# Esquem_tico.net
KiCad netlist of a schematic drawn in Altium Designer
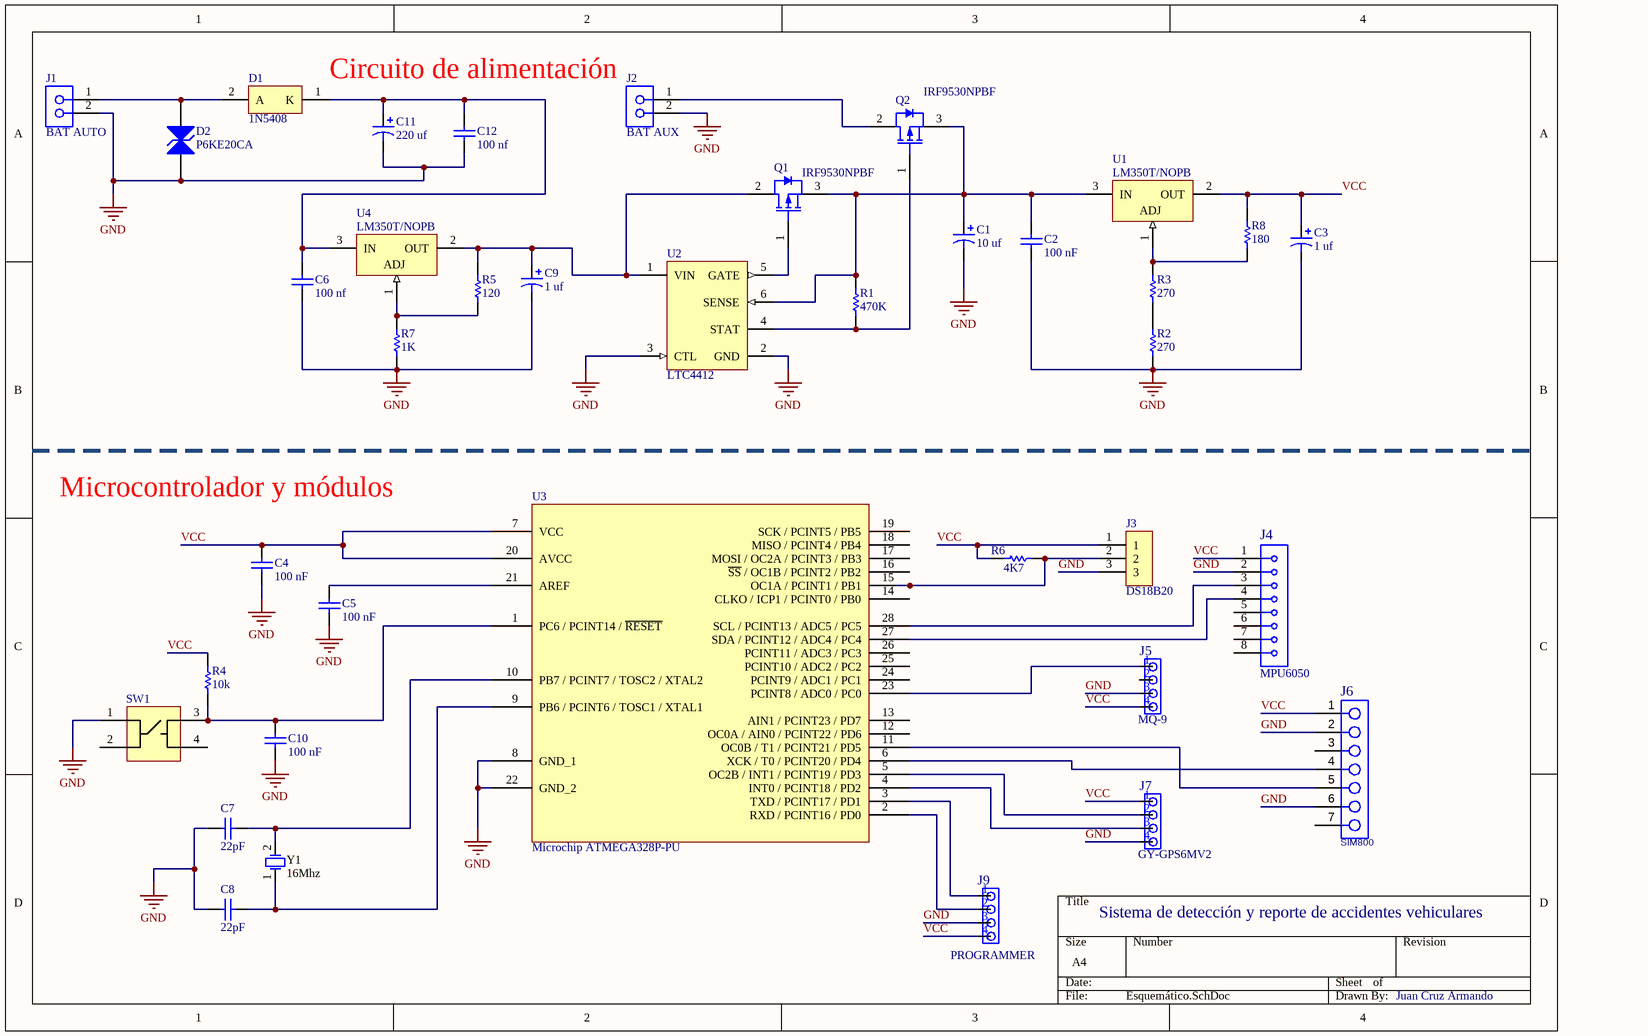
[diagram p0: Esquemático.SchDoc]

(export (version "E")
  (design (tool "Eeschema 10.0.6"))
  (components
    (comp (ref "C1")
      (value "10 uf")
      (footprint "PCB-imxzc0h3ulzopa7zwnih-1")
      (description "Capacitor Tantalum Solid 10uF 25V 10% (5.5 X 9mm) Radial 2.5mm 2.5 Ohm 125C Bulk")
      (fields (field (name "MANUFACTURER PART NUMBER") "TAP106K025SCS") (field (name "MANUFACTURER") "AVX"))
      (libsource (lib "My Personal Space") (part "SYM-82d04bdab8195d17-1"))
    )
    (comp (ref "C2")
      (value "100 nF")
      (footprint "PCB-ql28fbuo3tond8refhb5-1")
      (description "K 100nF Ceramic Multilayer Capacitor, 50 V dc, +125degC, X7R Dielectric, +/-10%")
      (libsource (lib "My Personal Space") (part "SYM-1272d9258f2acdb5-2"))
    )
    (comp (ref "C3")
      (value "1 uf")
      (footprint "PCB-acyh3aj9bk846069dhs3-1")
      (description "VR Series 1 uF 50 V 85°C Ø5 x 11 mm LS=2mm Radial Aluminum Electrolytic Cap")
      (libsource (lib "My Personal Space") (part "SYM-ee3b2732de2731fc-1"))
    )
    (comp (ref "C4")
      (value "100 nF")
      (footprint "PCB-cdnsso2r2iuvlncjnkpk-1")
      (description "100nF ceramic capacitor")
      (fields (field (name "MANUFACTURER PART NUMBER") "K104K10X7RF5UH5"))
      (libsource (lib "My Personal Space") (part "FG24C0G2W331JNT06"))
    )
    (comp (ref "C5")
      (value "100 nF")
      (footprint "PCB-cdnsso2r2iuvlncjnkpk-1")
      (description "100nF ceramic capacitor")
      (fields (field (name "MANUFACTURER PART NUMBER") "K104K10X7RF5UH5"))
      (libsource (lib "My Personal Space") (part "FG24C0G2W331JNT06"))
    )
    (comp (ref "C6")
      (value "100 nf")
      (footprint "PCB-ql28fbuo3tond8refhb5-1")
      (description "K 100nF Ceramic Multilayer Capacitor, 50 V dc, +125degC, X7R Dielectric, +/-10%")
      (libsource (lib "My Personal Space") (part "SYM-1272d9258f2acdb5-2"))
    )
    (comp (ref "C7")
      (value "22pF")
      (footprint "PCB-tqy8x0fx5p36cua9t83l-1")
      (description "Cap Ceramic 22pF 50V C0G 5% Radial 2.5mm 125°C Bulk")
      (libsource (lib "My Personal Space") (part "SYM-0071cbfa31a6dfb6-1"))
    )
    (comp (ref "C8")
      (value "22pF")
      (footprint "PCB-tqy8x0fx5p36cua9t83l-1")
      (description "Cap Ceramic 22pF 50V C0G 5% Radial 2.5mm 125°C Bulk")
      (libsource (lib "My Personal Space") (part "SYM-0071cbfa31a6dfb6-1"))
    )
    (comp (ref "C9")
      (value "1 uf")
      (footprint "PCB-acyh3aj9bk846069dhs3-1")
      (description "VR Series 1 uF 50 V 85°C Ø5 x 11 mm LS=2mm Radial Aluminum Electrolytic Cap")
      (libsource (lib "My Personal Space") (part "SYM-ee3b2732de2731fc-1"))
    )
    (comp (ref "C10")
      (value "100 nF")
      (footprint "PCB-cdnsso2r2iuvlncjnkpk-1")
      (description "100nF ceramic capacitor")
      (fields (field (name "MANUFACTURER PART NUMBER") "K104K10X7RF5UH5"))
      (libsource (lib "My Personal Space") (part "FG24C0G2W331JNT06"))
    )
    (comp (ref "C11")
      (value "220 uf")
      (footprint "PCB-imxzc0h3ulzopa7zwnih-1")
      (description "Capacitor Tantalum Solid 10uF 25V 10% (5.5 X 9mm) Radial 2.5mm 2.5 Ohm 125C Bulk")
      (fields (field (name "MANUFACTURER PART NUMBER") "TAP106K025SCS") (field (name "MANUFACTURER") "AVX"))
      (libsource (lib "My Personal Space") (part "SYM-82d04bdab8195d17-1"))
    )
    (comp (ref "C12")
      (value "100 nf")
      (footprint "PCB-ql28fbuo3tond8refhb5-1")
      (description "K 100nF Ceramic Multilayer Capacitor, 50 V dc, +125degC, X7R Dielectric, +/-10%")
      (libsource (lib "My Personal Space") (part "SYM-1272d9258f2acdb5-2"))
    )
    (comp (ref "D1")
      (value "1N5408")
      (footprint "ONSC-AXIAL_LEAD-2-267-05_V")
      (description "Standard Recovery Rectifier, 2-Pin Axial_Lead, Pb-Free, Tape and Reel")
      (fields (field (name "MANUFACTURER PART NUMBER") "1N5408RLG"))
      (libsource (lib "My Personal Space") (part "ONSC-D-K1A2-2_A"))
    )
    (comp (ref "D2")
      (value "P6KE20CA")
      (footprint "PCB-4dyrkuvni5xning65e4c-1")
      (description "In a Pack of 5, ON Semiconductor P6KE20CA, Bi-Directional TVS Diode, 600W, 2-Pin DO-15")
      (libsource (lib "My Personal Space") (part "SYM-eff326f9b9a13034-1"))
    )
    (comp (ref "J1")
      (value "BAT AUTO")
      (footprint "PCB-kiok1jlp9o9fcwf1wwvf-1")
      (description "Block, Terminal; 13.5 A; 250 V; 5 mm; 26 to 16 AWG; 2; Screw; Solder; 4 kV; PA")
      (libsource (lib "My Personal Space") (part "SYM-7ad9b3d37ed8a51e-1"))
    )
    (comp (ref "J2")
      (value "BAT AUX")
      (footprint "PCB-kiok1jlp9o9fcwf1wwvf-1")
      (description "Block, Terminal; 13.5 A; 250 V; 5 mm; 26 to 16 AWG; 2; Screw; Solder; 4 kV; PA")
      (libsource (lib "My Personal Space") (part "SYM-7ad9b3d37ed8a51e-1"))
    )
    (comp (ref "J3")
      (value "DS18B20")
      (footprint "PCB-t3j82fujp56a0y7cbkwq-1")
      (description "AMPMODU 3 Position Through-Hole Single Row 0.1 Inch Straight Breakaway Header")
      (fields (field (name "MANUFACTURER PART NUMBER") "5-146281-3"))
      (libsource (lib "My Personal Space") (part "SYM-56249debc17089e3-7"))
    )
    (comp (ref "J4")
      (value "MPU6050")
      (footprint "PCB-zdm29xznpx2fif9lk3na-1")
      (description "Conn Unshrouded Header HDR 8 POS 2.54mm Solder ST Top Entry Thru-Hole Bag/Box")
      (libsource (lib "My Personal Space") (part "SYM-1d33d663ca37c2f4-2"))
    )
    (comp (ref "J5")
      (value "MQ-9")
      (footprint "PCB-0bfjvpkufifbx95u45yw-1")
      (description "5-146274-4 ; ROHS ; TYCO ; AMPMODU Breakaway Heade rs 4P HEADER TIN single r ow")
      (fields (field (name "MANUFACTURER PART NUMBER") "5-146274-4"))
      (libsource (lib "My Personal Space") (part "SYM-ce480524f220118f-1"))
    )
    (comp (ref "J6")
      (value "SIM800")
      (footprint "PCBComponent_1")
      (description "Conn Unshrouded Header HDR 7 POS 2.54mm Solder ST Thru-Hole")
      (fields (field (name "MANUFACTURER PART NUMBER") "5-146280-7"))
      (libsource (lib "My Personal Space") (part "TE Connectivity 5-146280-7"))
    )
    (comp (ref "J7")
      (value "GY-GPS6MV2")
      (footprint "PCB-0bfjvpkufifbx95u45yw-1")
      (description "5-146274-4 ; ROHS ; TYCO ; AMPMODU Breakaway Heade rs 4P HEADER TIN single r ow")
      (fields (field (name "MANUFACTURER PART NUMBER") "5-146274-4"))
      (libsource (lib "My Personal Space") (part "SYM-ce480524f220118f-1"))
    )
    (comp (ref "J9")
      (value "PROGRAMMER")
      (footprint "PCB-0bfjvpkufifbx95u45yw-1")
      (description "5-146274-4 ; ROHS ; TYCO ; AMPMODU Breakaway Heade rs 4P HEADER TIN single r ow")
      (fields (field (name "MANUFACTURER PART NUMBER") "5-146274-4"))
      (libsource (lib "My Personal Space") (part "SYM-ce480524f220118f-1"))
    )
    (comp (ref "Q1")
      (value "IRF9530NPBF")
      (footprint "Infineon IRF9530NPBF-Footprint-1")
      (description "Mosfet, Power; P-ch; Vdss -100V; Rds(on) 0.2 Ohm; Id -14A; TO-220AB; Pd 79W; Vgs +/-20V")
      (libsource (lib "My Personal Space") (part "IRF9530N"))
    )
    (comp (ref "Q2")
      (value "IRF9530NPBF")
      (footprint "Infineon IRF9530NPBF-Footprint-1")
      (description "Mosfet, Power; P-ch; Vdss -100V; Rds(on) 0.2 Ohm; Id -14A; TO-220AB; Pd 79W; Vgs +/-20V")
      (libsource (lib "My Personal Space") (part "IRF9530N"))
    )
    (comp (ref "R1")
      (value "470K")
      (footprint "Yageo CFR-25JT-52-470K-Footprint-1")
      (description "Res Carbon Film 470K Ohm 5% 0.25W(1/4W) -700ppm/C to 0ppm/C Conformal Coated AXL Tape and Box")
      (fields (field (name "MANUFACTURER PART NUMBER") "CFR-25JT-52-470K"))
      (libsource (lib "My Personal Space") (part "RES-2"))
    )
    (comp (ref "R2")
      (value "270")
      (footprint "PCB-akkdcmgfauh1vh9d0cz2-1")
      (description "General Purpose Mini Metal Film Leaded Resistor")
      (fields (field (name "MANUFACTURER PART NUMBER") "RNMF14FTC120R"))
      (libsource (lib "My Personal Space") (part "SYM-2e58e67d59dbf19f-1"))
    )
    (comp (ref "R3")
      (value "270")
      (footprint "PCB-akkdcmgfauh1vh9d0cz2-1")
      (description "General Purpose Mini Metal Film Leaded Resistor")
      (fields (field (name "MANUFACTURER PART NUMBER") "RNMF14FTC120R"))
      (libsource (lib "My Personal Space") (part "SYM-2e58e67d59dbf19f-1"))
    )
    (comp (ref "R4")
      (value "10k")
      (footprint "PCB-srwdokf50franrk04i3o-1")
      (description "R Series Axial Through Hole Fixed Resistor 10kOhms +/-0.1% 0.25W +/-15ppm/degC")
      (fields (field (name "MANUFACTURER PART NUMBER") "YR1B10KCC"))
      (libsource (lib "My Personal Space") (part "SYM-7662bf3a2cc5a9a5-3"))
    )
    (comp (ref "R5")
      (value "120")
      (footprint "PCB-akkdcmgfauh1vh9d0cz2-1")
      (description "General Purpose Mini Metal Film Leaded Resistor")
      (fields (field (name "MANUFACTURER PART NUMBER") "RNMF14FTC120R"))
      (libsource (lib "My Personal Space") (part "SYM-2e58e67d59dbf19f-1"))
    )
    (comp (ref "R6")
      (value "4K7")
      (footprint "PCB-jdq3crg2pt2ynotio4yr-1")
      (description "Res Carbon Film 4.7K Ohm 5% 1/4W -500ppm/°C to 350ppm/°C Conformal AXL Thru-Hole Paper T/R")
      (fields (field (name "MANUFACTURER PART NUMBER") "CFR-25JR-52-4K7"))
      (libsource (lib "My Personal Space") (part "SYM-d9fa11ede6f3063d-1"))
    )
    (comp (ref "R7")
      (value "1K")
      (footprint "Yageo CFR-25JT-52-470K-Footprint-1")
      (description "Res Carbon Film 470K Ohm 5% 0.25W(1/4W) -700ppm/C to 0ppm/C Conformal Coated AXL Tape and Box")
      (fields (field (name "MANUFACTURER PART NUMBER") "CFR-25JT-52-470K"))
      (libsource (lib "My Personal Space") (part "RES-2"))
    )
    (comp (ref "R8")
      (value "180")
      (footprint "PCB-akkdcmgfauh1vh9d0cz2-1")
      (description "General Purpose Mini Metal Film Leaded Resistor")
      (fields (field (name "MANUFACTURER PART NUMBER") "RNMF14FTC120R"))
      (libsource (lib "My Personal Space") (part "SYM-2e58e67d59dbf19f-1"))
    )
    (comp (ref "SW1")
      (value "E-Switch TL1105BF250Q")
      (footprint "PCB-w1cc0e0zrtxe6z7oi7lq-1")
      (description "Switch Tactile N.O. SPST Round Button PC Pins 0.05A 50VDC 2.45N Thru-Hole")
      (fields (field (name "MANUFACTURER PART NUMBER") "TL1105BF250Q"))
      (libsource (lib "My Personal Space") (part "SYM-40908b1e9ad09f57-1"))
    )
    (comp (ref "U1")
      (value "LM350T/NOPB")
      (footprint "T03B")
      (description "LDO")
      (libsource (lib "My Personal Space") (part "PM-REG-LM1086ADJ-SIL3"))
    )
    (comp (ref "U2")
      (value "LTC4412")
      (footprint "LT-S6-6-TSOT-23_L")
      (fields (field (name "MANUFACTURER PART NUMBER") "LTC4412HVIS6#TRPBF"))
      (libsource (lib "My Personal Space") (part "LT-LTC4412_HV-S6-6"))
    )
    (comp (ref "U3")
      (value "Microchip ATMEGA328P-PU")
      (footprint "PCB-n0zq5lox7fck5k780cz8-1")
      (description "ATMEGA328P-PU; 8 bit Microcontroller AVR 20MHz 1; 32kb Flash; 2kb RAM; I2C SPI 2")
      (fields (field (name "MANUFACTURER PART NUMBER") "ATMEGA328P-PU") (field (name "MANUFACTURER") "Atmel"))
      (libsource (lib "My Personal Space") (part "SYM-60cead66c348bf09-22"))
    )
    (comp (ref "U4")
      (value "LM350T/NOPB")
      (footprint "T03B")
      (description "LDO")
      (libsource (lib "My Personal Space") (part "PM-REG-LM1086ADJ-SIL3"))
    )
    (comp (ref "Y1")
      (value "16Mhz")
      (footprint "FOX-FOXSLF160-20")
      (description "Resistance Weld Thru-Hole Crystal, 16 MHz, -20 to 70 degC, 2-Pin THD, RoHS, Bulk")
      (fields (field (name "MANUFACTURER PART NUMBER") "FOXSLF/160-20"))
      (libsource (lib "My Personal Space") (part "XTAL-1-2-2"))
    )
  )
  (nets
    (net (code "2") (name "/VCC") (class "Default")
      (node (ref "C3") (pin "1") (pinfunction "1_1") (pintype "passive"))
      (node (ref "C4") (pin "2") (pinfunction "2_2") (pintype "passive"))
      (node (ref "J3") (pin "1") (pinfunction "1_1") (pintype "passive"))
      (node (ref "J4") (pin "1") (pinfunction "1_1") (pintype "passive"))
      (node (ref "J5") (pin "4") (pinfunction "4_4") (pintype "passive"))
      (node (ref "J6") (pin "1") (pinfunction "1_1") (pintype "passive"))
      (node (ref "J7") (pin "1") (pinfunction "1_1") (pintype "passive"))
      (node (ref "J9") (pin "4") (pinfunction "4_4") (pintype "passive"))
      (node (ref "R4") (pin "2") (pinfunction "2_2") (pintype "passive"))
      (node (ref "R6") (pin "1") (pinfunction "1_1") (pintype "passive"))
      (node (ref "R8") (pin "2") (pinfunction "2_2") (pintype "passive"))
      (node (ref "U1") (pin "2") (pinfunction "OUT_2") (pintype "power_in"))
      (node (ref "U3") (pin "20") (pinfunction "AVCC_20") (pintype "passive"))
      (node (ref "U3") (pin "7") (pinfunction "VCC_7") (pintype "passive"))
    )
    (net (code "3") (name "GND") (class "Default")
      (node (ref "C1") (pin "2") (pinfunction "2_2") (pintype "passive"))
      (node (ref "C10") (pin "1") (pinfunction "1_1") (pintype "passive"))
      (node (ref "C11") (pin "2") (pinfunction "2_2") (pintype "passive"))
      (node (ref "C12") (pin "1") (pinfunction "1_1") (pintype "passive"))
      (node (ref "C2") (pin "1") (pinfunction "1_1") (pintype "passive"))
      (node (ref "C3") (pin "2") (pinfunction "2_2") (pintype "passive"))
      (node (ref "C4") (pin "1") (pinfunction "1_1") (pintype "passive"))
      (node (ref "C5") (pin "1") (pinfunction "1_1") (pintype "passive"))
      (node (ref "C6") (pin "1") (pinfunction "1_1") (pintype "passive"))
      (node (ref "C7") (pin "1") (pinfunction "1_1") (pintype "passive"))
      (node (ref "C8") (pin "1") (pinfunction "1_1") (pintype "passive"))
      (node (ref "C9") (pin "2") (pinfunction "2_2") (pintype "passive"))
      (node (ref "D2") (pin "1") (pinfunction "A_1") (pintype "passive"))
      (node (ref "J1") (pin "2") (pinfunction "2_2") (pintype "passive"))
      (node (ref "J2") (pin "2") (pinfunction "2_2") (pintype "passive"))
      (node (ref "J3") (pin "3") (pinfunction "3_3") (pintype "passive"))
      (node (ref "J4") (pin "2") (pinfunction "2_2") (pintype "passive"))
      (node (ref "J5") (pin "3") (pinfunction "3_3") (pintype "passive"))
      (node (ref "J6") (pin "2") (pinfunction "2_2") (pintype "passive"))
      (node (ref "J6") (pin "6") (pinfunction "6_6") (pintype "passive"))
      (node (ref "J7") (pin "4") (pinfunction "4_4") (pintype "passive"))
      (node (ref "J9") (pin "3") (pinfunction "3_3") (pintype "passive"))
      (node (ref "R2") (pin "1") (pinfunction "1_1") (pintype "passive"))
      (node (ref "R7") (pin "1") (pinfunction "1_1") (pintype "passive"))
      (node (ref "SW1") (pin "1") (pinfunction "1_1") (pintype "passive"))
      (node (ref "U2") (pin "2") (pinfunction "GND_2") (pintype "power_in"))
      (node (ref "U2") (pin "3") (pinfunction "CTL_3") (pintype "input"))
      (node (ref "U3") (pin "22") (pinfunction "GND_2_22") (pintype "passive"))
      (node (ref "U3") (pin "8") (pinfunction "GND_1_8") (pintype "passive"))
    )
    (net (code "4") (name "Net-(D1-A)") (class "Default")
      (node (ref "D1") (pin "2") (pinfunction "A_2") (pintype "passive"))
      (node (ref "D2") (pin "2") (pinfunction "K_2") (pintype "passive"))
      (node (ref "J1") (pin "1") (pinfunction "1_1") (pintype "passive"))
    )
    (net (code "5") (name "Net-(D1-K)") (class "Default")
      (node (ref "C11") (pin "1") (pinfunction "1_1") (pintype "passive"))
      (node (ref "C12") (pin "2") (pinfunction "2_2") (pintype "passive"))
      (node (ref "C6") (pin "2") (pinfunction "2_2") (pintype "passive"))
      (node (ref "D1") (pin "1") (pinfunction "K_1") (pintype "passive"))
      (node (ref "U4") (pin "3") (pinfunction "IN_3") (pintype "power_in"))
    )
    (net (code "6") (name "Net-(Q1-D)") (class "Default")
      (node (ref "C9") (pin "1") (pinfunction "1_1") (pintype "passive"))
      (node (ref "Q1") (pin "2") (pinfunction "D_2") (pintype "passive"))
      (node (ref "R5") (pin "2") (pinfunction "2_2") (pintype "passive"))
      (node (ref "U2") (pin "1") (pinfunction "VIN_1") (pintype "power_in"))
      (node (ref "U4") (pin "2") (pinfunction "OUT_2") (pintype "power_in"))
    )
    (net (code "7") (name "Net-(Q1-G)") (class "Default")
      (node (ref "Q1") (pin "1") (pinfunction "G_1") (pintype "passive"))
      (node (ref "U2") (pin "5") (pinfunction "GATE_5") (pintype "output"))
    )
    (net (code "8") (name "Net-(Q1-S)") (class "Default")
      (node (ref "C1") (pin "1") (pinfunction "1_1") (pintype "passive"))
      (node (ref "C2") (pin "2") (pinfunction "2_2") (pintype "passive"))
      (node (ref "Q1") (pin "3") (pinfunction "S_3") (pintype "passive"))
      (node (ref "Q2") (pin "3") (pinfunction "S_3") (pintype "passive"))
      (node (ref "R1") (pin "2") (pinfunction "2_2") (pintype "passive"))
      (node (ref "U1") (pin "3") (pinfunction "IN_3") (pintype "power_in"))
      (node (ref "U2") (pin "6") (pinfunction "SENSE_6") (pintype "input"))
    )
    (net (code "9") (name "Net-(Q2-D)") (class "Default")
      (node (ref "J2") (pin "1") (pinfunction "1_1") (pintype "passive"))
      (node (ref "Q2") (pin "2") (pinfunction "D_2") (pintype "passive"))
    )
    (net (code "10") (name "Net-(Q2-G)") (class "Default")
      (node (ref "Q2") (pin "1") (pinfunction "G_1") (pintype "passive"))
      (node (ref "R1") (pin "1") (pinfunction "1_1") (pintype "passive"))
      (node (ref "U2") (pin "4") (pinfunction "STAT_4") (pintype "open_collector"))
    )
    (net (code "11") (name "Net-(R2-Pad2)") (class "Default")
      (node (ref "R2") (pin "2") (pinfunction "2_2") (pintype "passive"))
      (node (ref "R3") (pin "1") (pinfunction "1_1") (pintype "passive"))
    )
    (net (code "12") (name "Net-(U1-ADJ)") (class "Default")
      (node (ref "R3") (pin "2") (pinfunction "2_2") (pintype "passive"))
      (node (ref "R8") (pin "1") (pinfunction "1_1") (pintype "passive"))
      (node (ref "U1") (pin "1") (pinfunction "ADJ_1") (pintype "input"))
    )
    (net (code "13") (name "Net-(U3-AREF)") (class "Default")
      (node (ref "C5") (pin "2") (pinfunction "2_2") (pintype "passive"))
      (node (ref "U3") (pin "21") (pinfunction "AREF_21") (pintype "passive"))
    )
    (net (code "14") (name "Net-(U3-INT0_{slash}_PCINT18_{slash}_PD2)") (class "Default")
      (node (ref "J7") (pin "3") (pinfunction "3_3") (pintype "passive"))
      (node (ref "U3") (pin "4") (pinfunction "INT0_/_PCINT18_/_PD2_4") (pintype "passive"))
    )
    (net (code "15") (name "Net-(U3-OC0B_{slash}_T1_{slash}_PCINT21_{slash}_PD5)") (class "Default")
      (node (ref "J6") (pin "5") (pinfunction "5_5") (pintype "passive"))
      (node (ref "U3") (pin "11") (pinfunction "OC0B_/_T1_/_PCINT21_/_PD5_11") (pintype "passive"))
    )
    (net (code "16") (name "Net-(U3-OC1A_{slash}_PCINT1_{slash}_PB1)") (class "Default")
      (node (ref "J3") (pin "2") (pinfunction "2_2") (pintype "passive"))
      (node (ref "R6") (pin "2") (pinfunction "2_2") (pintype "passive"))
      (node (ref "U3") (pin "15") (pinfunction "OC1A_/_PCINT1_/_PB1_15") (pintype "passive"))
    )
    (net (code "17") (name "Net-(U3-OC2B_{slash}_INT1_{slash}_PCINT19_{slash}_PD3)") (class "Default")
      (node (ref "J7") (pin "2") (pinfunction "2_2") (pintype "passive"))
      (node (ref "U3") (pin "5") (pinfunction "OC2B_/_INT1_/_PCINT19_/_PD3_5") (pintype "passive"))
    )
    (net (code "18") (name "Net-(U3-PB6_{slash}_PCINT6_{slash}_TOSC1_{slash}_XTAL1)") (class "Default")
      (node (ref "C8") (pin "2") (pinfunction "2_2") (pintype "passive"))
      (node (ref "U3") (pin "9") (pinfunction "PB6_/_PCINT6_/_TOSC1_/_XTAL1_9") (pintype "passive"))
      (node (ref "Y1") (pin "1") (pinfunction "1_1") (pintype "passive"))
    )
    (net (code "19") (name "Net-(U3-PB7_{slash}_PCINT7_{slash}_TOSC2_{slash}_XTAL2)") (class "Default")
      (node (ref "C7") (pin "2") (pinfunction "2_2") (pintype "passive"))
      (node (ref "U3") (pin "10") (pinfunction "PB7_/_PCINT7_/_TOSC2_/_XTAL2_10") (pintype "passive"))
      (node (ref "Y1") (pin "2") (pinfunction "2_2") (pintype "passive"))
    )
    (net (code "20") (name "Net-(U3-PC6_{slash}_PCINT14_{slash}_~{RESET})") (class "Default")
      (node (ref "C10") (pin "2") (pinfunction "2_2") (pintype "passive"))
      (node (ref "R4") (pin "1") (pinfunction "1_1") (pintype "passive"))
      (node (ref "SW1") (pin "3") (pinfunction "3_3") (pintype "passive"))
      (node (ref "U3") (pin "1") (pinfunction "PC6_/_PCINT14_/_~{RESET}_1") (pintype "passive"))
    )
    (net (code "21") (name "Net-(U3-PCINT8_{slash}_ADC0_{slash}_PC0)") (class "Default")
      (node (ref "J5") (pin "1") (pinfunction "1_1") (pintype "passive"))
      (node (ref "U3") (pin "23") (pinfunction "PCINT8_/_ADC0_/_PC0_23") (pintype "passive"))
    )
    (net (code "22") (name "Net-(U3-RXD_{slash}_PCINT16_{slash}_PD0)") (class "Default")
      (node (ref "J9") (pin "2") (pinfunction "2_2") (pintype "passive"))
      (node (ref "U3") (pin "2") (pinfunction "RXD_/_PCINT16_/_PD0_2") (pintype "passive"))
    )
    (net (code "23") (name "Net-(U3-SCL_{slash}_PCINT13_{slash}_ADC5_{slash}_PC5)") (class "Default")
      (node (ref "J4") (pin "3") (pinfunction "3_3") (pintype "passive"))
      (node (ref "U3") (pin "28") (pinfunction "SCL_/_PCINT13_/_ADC5_/_PC5_28") (pintype "passive"))
    )
    (net (code "24") (name "Net-(U3-SDA_{slash}_PCINT12_{slash}_ADC4_{slash}_PC4)") (class "Default")
      (node (ref "J4") (pin "4") (pinfunction "4_4") (pintype "passive"))
      (node (ref "U3") (pin "27") (pinfunction "SDA_/_PCINT12_/_ADC4_/_PC4_27") (pintype "passive"))
    )
    (net (code "25") (name "Net-(U3-TXD_{slash}_PCINT17_{slash}_PD1)") (class "Default")
      (node (ref "J9") (pin "1") (pinfunction "1_1") (pintype "passive"))
      (node (ref "U3") (pin "3") (pinfunction "TXD_/_PCINT17_/_PD1_3") (pintype "passive"))
    )
    (net (code "26") (name "Net-(U3-XCK_{slash}_T0_{slash}_PCINT20_{slash}_PD4)") (class "Default")
      (node (ref "J6") (pin "4") (pinfunction "4_4") (pintype "passive"))
      (node (ref "U3") (pin "6") (pinfunction "XCK_/_T0_/_PCINT20_/_PD4_6") (pintype "passive"))
    )
    (net (code "27") (name "Net-(U4-ADJ)") (class "Default")
      (node (ref "R5") (pin "1") (pinfunction "1_1") (pintype "passive"))
      (node (ref "R7") (pin "2") (pinfunction "2_2") (pintype "passive"))
      (node (ref "U4") (pin "1") (pinfunction "ADJ_1") (pintype "input"))
    )
    (net (code "28") (name "unconnected-(J4-Pad5)") (class "Default")
      (node (ref "J4") (pin "5") (pinfunction "5_5") (pintype "passive"))
    )
    (net (code "29") (name "unconnected-(J4-Pad6)") (class "Default")
      (node (ref "J4") (pin "6") (pinfunction "6_6") (pintype "passive"))
    )
    (net (code "30") (name "unconnected-(J4-Pad7)") (class "Default")
      (node (ref "J4") (pin "7") (pinfunction "7_7") (pintype "passive"))
    )
    (net (code "31") (name "unconnected-(J4-Pad8)") (class "Default")
      (node (ref "J4") (pin "8") (pinfunction "8_8") (pintype "passive"))
    )
    (net (code "32") (name "unconnected-(J5-Pad2)") (class "Default")
      (node (ref "J5") (pin "2") (pinfunction "2_2") (pintype "passive"))
    )
    (net (code "33") (name "unconnected-(J6-Pad3)") (class "Default")
      (node (ref "J6") (pin "3") (pinfunction "3_3") (pintype "passive"))
    )
    (net (code "34") (name "unconnected-(J6-Pad7)") (class "Default")
      (node (ref "J6") (pin "7") (pinfunction "7_7") (pintype "passive"))
    )
    (net (code "35") (name "unconnected-(SW1-Pad2)") (class "Default")
      (node (ref "SW1") (pin "2") (pinfunction "2_2") (pintype "passive"))
    )
    (net (code "36") (name "unconnected-(SW1-Pad4)") (class "Default")
      (node (ref "SW1") (pin "4") (pinfunction "4_4") (pintype "passive"))
    )
    (net (code "37") (name "unconnected-(U3-AIN1_{slash}_PCINT23_{slash}_PD7-Pad13)") (class "Default")
      (node (ref "U3") (pin "13") (pinfunction "AIN1_/_PCINT23_/_PD7_13") (pintype "passive"))
    )
    (net (code "38") (name "unconnected-(U3-CLKO_{slash}_ICP1_{slash}_PCINT0_{slash}_PB0-Pad14)") (class "Default")
      (node (ref "U3") (pin "14") (pinfunction "CLKO_/_ICP1_/_PCINT0_/_PB0_14") (pintype "passive"))
    )
    (net (code "39") (name "unconnected-(U3-MISO_{slash}_PCINT4_{slash}_PB4-Pad18)") (class "Default")
      (node (ref "U3") (pin "18") (pinfunction "MISO_/_PCINT4_/_PB4_18") (pintype "passive"))
    )
    (net (code "40") (name "unconnected-(U3-MOSI_{slash}_OC2A_{slash}_PCINT3_{slash}_PB3-Pad17)") (class "Default")
      (node (ref "U3") (pin "17") (pinfunction "MOSI_/_OC2A_/_PCINT3_/_PB3_17") (pintype "passive"))
    )
    (net (code "41") (name "unconnected-(U3-OC0A_{slash}_AIN0_{slash}_PCINT22_{slash}_PD6-Pad12)") (class "Default")
      (node (ref "U3") (pin "12") (pinfunction "OC0A_/_AIN0_/_PCINT22_/_PD6_12") (pintype "passive"))
    )
    (net (code "42") (name "unconnected-(U3-PCINT9_{slash}_ADC1_{slash}_PC1-Pad24)") (class "Default")
      (node (ref "U3") (pin "24") (pinfunction "PCINT9_/_ADC1_/_PC1_24") (pintype "passive"))
    )
    (net (code "43") (name "unconnected-(U3-PCINT10_{slash}_ADC2_{slash}_PC2-Pad25)") (class "Default")
      (node (ref "U3") (pin "25") (pinfunction "PCINT10_/_ADC2_/_PC2_25") (pintype "passive"))
    )
    (net (code "44") (name "unconnected-(U3-PCINT11_{slash}_ADC3_{slash}_PC3-Pad26)") (class "Default")
      (node (ref "U3") (pin "26") (pinfunction "PCINT11_/_ADC3_/_PC3_26") (pintype "passive"))
    )
    (net (code "45") (name "unconnected-(U3-SCK_{slash}_PCINT5_{slash}_PB5-Pad19)") (class "Default")
      (node (ref "U3") (pin "19") (pinfunction "SCK_/_PCINT5_/_PB5_19") (pintype "passive"))
    )
    (net (code "46") (name "unconnected-(U3-~{SS}_{slash}_OC1B_{slash}_PCINT2_{slash}_PB2-Pad16)") (class "Default")
      (node (ref "U3") (pin "16") (pinfunction "~{SS}_/_OC1B_/_PCINT2_/_PB2_16") (pintype "passive"))
    )
  )
)
